# ControllerV2_0_2.net
KiCad netlist of a schematic drawn in Altium Designer
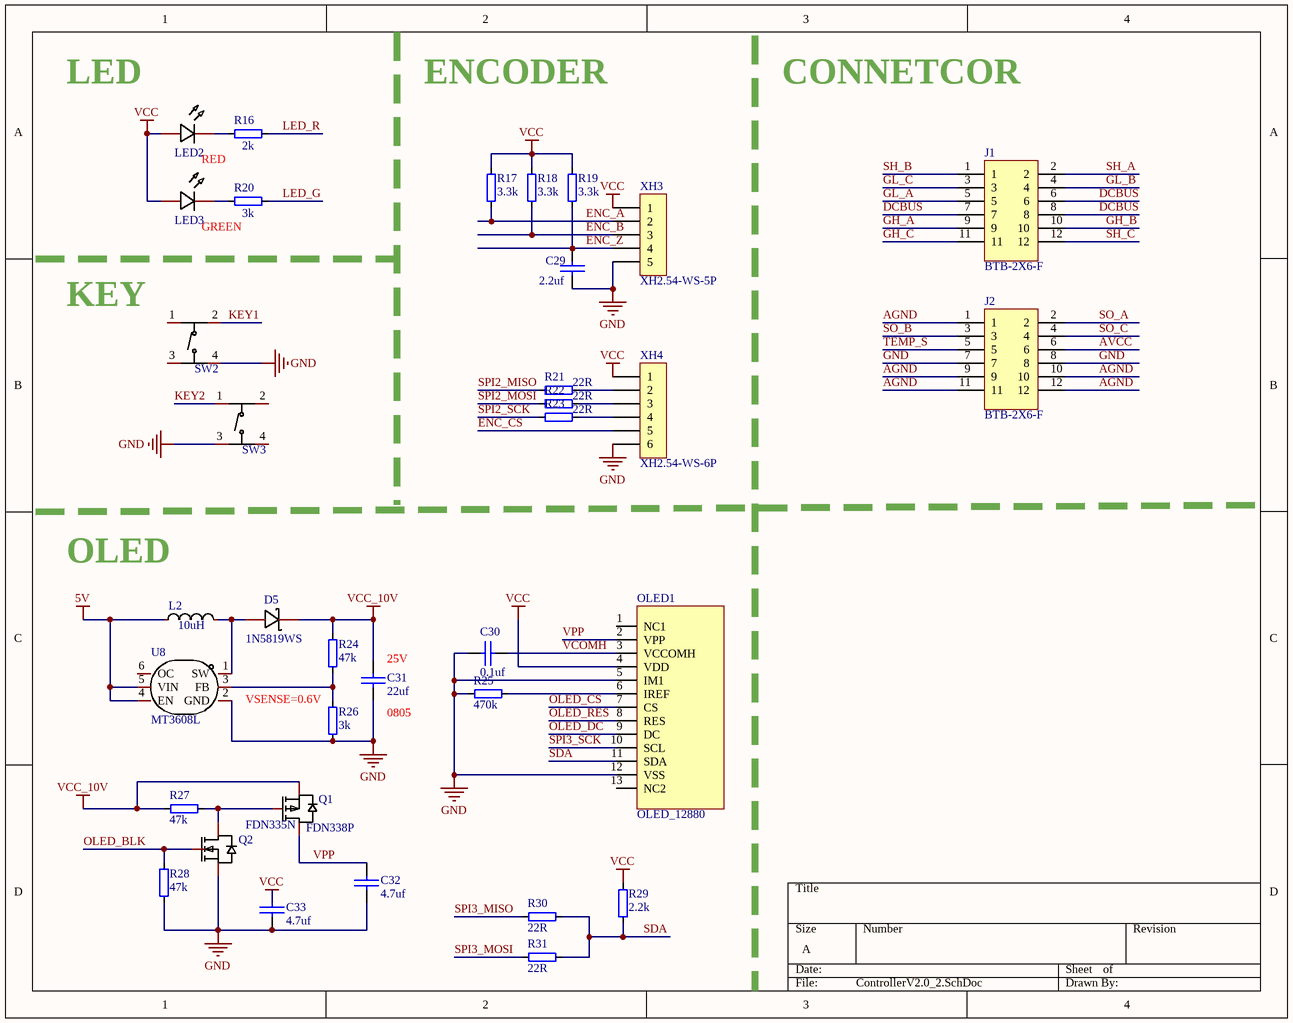
[diagram p0: ControllerV2.0_2.SchDoc]

(export (version "E")
  (design (tool "Eeschema 10.0.6"))
  (components
    (comp (ref "C29")
      (value "2.2uf")
      (footprint "0603C")
      (description "贴片电容")
      (libsource (lib "Controller") (part "CAP"))
    )
    (comp (ref "C30")
      (value "0.1uf")
      (footprint "0603C")
      (description "贴片电容")
      (libsource (lib "Controller") (part "CAP"))
    )
    (comp (ref "C31")
      (value "22uf")
      (footprint "0805C")
      (description "贴片电容")
      (libsource (lib "Controller") (part "CAP"))
    )
    (comp (ref "C32")
      (value "4.7uf")
      (footprint "0603C")
      (description "贴片电容")
      (libsource (lib "Controller") (part "CAP"))
    )
    (comp (ref "C33")
      (value "4.7uf")
      (footprint "0603C")
      (description "贴片电容")
      (libsource (lib "Controller") (part "CAP"))
    )
    (comp (ref "D5")
      (value "1N5819WS")
      (footprint "SOD-323")
      (description "肖特基二极管")
      (fields (field (name "MANUFACTURER") "Hottech(合科泰)"))
      (libsource (lib "Controller") (part "1N5819WS"))
    )
    (comp (ref "J1")
      (value "BTB-2X6-F")
      (footprint "BTB-F-0.8mm-2x6P")
      (description "0.8间距2x6P母座")
      (libsource (lib "Controller") (part "BTB-2X6-F"))
    )
    (comp (ref "J2")
      (value "BTB-2X6-F")
      (footprint "BTB-F-0.8mm-2x6P")
      (description "0.8间距2x6P母座")
      (libsource (lib "Controller") (part "BTB-2X6-F"))
    )
    (comp (ref "L2")
      (value "10uH")
      (footprint "IND-SMD_L3.0-W3.0_SWPA3010S")
      (description "电感值:10uH;精度:±20%;额定电流:920mA;")
      (fields (field (name "MANUFACTURER") "SXN(顺翔诺)") (field (name "MANUFACTURER PART") "SMDRI74-220M"))
      (libsource (lib "Controller") (part "SWPA3015S100MT"))
    )
    (comp (ref "LED2")
      (value "LED_0603-B")
      (footprint "LED_0603")
      (libsource (lib "Controller") (part "LED"))
    )
    (comp (ref "LED3")
      (value "LED_0603-B")
      (footprint "LED_0603")
      (libsource (lib "Controller") (part "LED"))
    )
    (comp (ref "OLED1")
      (value "OLED_12880")
      (footprint "OLED_12880")
      (description "OLED_128*80")
      (libsource (lib "Controller") (part "OLED_12880"))
    )
    (comp (ref "Q1")
      (value "FDN338P")
      (footprint "SOT-23-3")
      (description "P沟道 耐压:20V 电流:2A")
      (fields (field (name "MANUFACTURER") "TECH PUBLIC(台舟)"))
      (libsource (lib "Controller") (part "FDN338P"))
    )
    (comp (ref "Q2")
      (value "FDN335N")
      (footprint "SOT-23-3")
      (description "N沟道 耐压:20V 电流:1.7A")
      (fields (field (name "MANUFACTURER") "TECH PUBLIC(台舟)"))
      (libsource (lib "Controller") (part "FDN335N"))
    )
    (comp (ref "R16")
      (value "2k")
      (footprint "0603R")
      (description "贴片电阻")
      (libsource (lib "Controller") (part "RES"))
    )
    (comp (ref "R17")
      (value "3.3k")
      (footprint "0603R")
      (description "贴片电阻")
      (libsource (lib "Controller") (part "RES"))
    )
    (comp (ref "R18")
      (value "3.3k")
      (footprint "0603R")
      (description "贴片电阻")
      (libsource (lib "Controller") (part "RES"))
    )
    (comp (ref "R19")
      (value "3.3k")
      (footprint "0603R")
      (description "贴片电阻")
      (libsource (lib "Controller") (part "RES"))
    )
    (comp (ref "R20")
      (value "3k")
      (footprint "0603R")
      (description "贴片电阻")
      (libsource (lib "Controller") (part "RES"))
    )
    (comp (ref "R21")
      (value "22R")
      (footprint "0603R")
      (description "贴片电阻")
      (libsource (lib "Controller") (part "RES"))
    )
    (comp (ref "R22")
      (value "22R")
      (footprint "0603R")
      (description "贴片电阻")
      (libsource (lib "Controller") (part "RES"))
    )
    (comp (ref "R23")
      (value "22R")
      (footprint "0603R")
      (description "贴片电阻")
      (libsource (lib "Controller") (part "RES"))
    )
    (comp (ref "R24")
      (value "47k")
      (footprint "0603R")
      (description "贴片电阻")
      (libsource (lib "Controller") (part "RES"))
    )
    (comp (ref "R25")
      (value "470k")
      (footprint "0603R")
      (description "贴片电阻")
      (libsource (lib "Controller") (part "RES"))
    )
    (comp (ref "R26")
      (value "3k")
      (footprint "0603R")
      (description "贴片电阻")
      (libsource (lib "Controller") (part "RES"))
    )
    (comp (ref "R27")
      (value "47k")
      (footprint "0603R")
      (description "贴片电阻")
      (libsource (lib "Controller") (part "RES"))
    )
    (comp (ref "R28")
      (value "47k")
      (footprint "0603R")
      (description "贴片电阻")
      (libsource (lib "Controller") (part "RES"))
    )
    (comp (ref "R29")
      (value "2.2k")
      (footprint "0603R")
      (description "贴片电阻")
      (libsource (lib "Controller") (part "RES"))
    )
    (comp (ref "R30")
      (value "22R")
      (footprint "0603R")
      (description "贴片电阻")
      (libsource (lib "Controller") (part "RES"))
    )
    (comp (ref "R31")
      (value "22R")
      (footprint "0603R")
      (description "贴片电阻")
      (libsource (lib "Controller") (part "RES"))
    )
    (comp (ref "SW2")
      (value "TS-1187A-B-A-B")
      (footprint "TSW SMD-4*4*1.5")
      (description "轻触开关")
      (fields (field (name "MANUFACTURER") "XKB Connectivity(中国星坤)"))
      (libsource (lib "Controller") (part "TS-1187A-B-A-B"))
    )
    (comp (ref "SW3")
      (value "TS-1187A-B-A-B")
      (footprint "TSW SMD-4*4*1.5")
      (description "轻触开关")
      (fields (field (name "MANUFACTURER") "XKB Connectivity(中国星坤)"))
      (libsource (lib "Controller") (part "TS-1187A-B-A-B"))
    )
    (comp (ref "U8")
      (value "MT3608L")
      (footprint "SOT-23-6")
      (fields (field (name "MANUFACTURER") "西安航天民芯"))
      (libsource (lib "Controller") (part "MT3608L"))
    )
    (comp (ref "XH3")
      (value "XH2.54-WS-5P")
      (footprint "XH2.54-WS-5P")
      (libsource (lib "Controller") (part "XH2.54-WS-5P"))
    )
    (comp (ref "XH4")
      (value "XH2.54-WS-6P")
      (footprint "XH2.54-WS-6P")
      (libsource (lib "Controller") (part "XH2.54-WS-6P"))
    )
  )
  (nets
    (net (code "1") (name "/AGND") (class "Default")
      (node (ref "J2") (pin "1") (pinfunction "1_1") (pintype "passive"))
      (node (ref "J2") (pin "10") (pinfunction "10_10") (pintype "passive"))
      (node (ref "J2") (pin "11") (pinfunction "11_11") (pintype "passive"))
      (node (ref "J2") (pin "12") (pinfunction "12_12") (pintype "passive"))
      (node (ref "J2") (pin "9") (pinfunction "9_9") (pintype "passive"))
    )
    (net (code "2") (name "/AVCC") (class "Default")
      (node (ref "J2") (pin "6") (pinfunction "6_6") (pintype "passive"))
    )
    (net (code "3") (name "/DCBUS") (class "Default")
      (node (ref "J1") (pin "6") (pinfunction "6_6") (pintype "passive"))
      (node (ref "J1") (pin "7") (pinfunction "7_7") (pintype "passive"))
      (node (ref "J1") (pin "8") (pinfunction "8_8") (pintype "passive"))
    )
    (net (code "4") (name "/ENC_A") (class "Default")
      (node (ref "R17") (pin "1") (pinfunction "1_1") (pintype "passive"))
      (node (ref "XH3") (pin "2") (pinfunction "2_2") (pintype "passive"))
    )
    (net (code "5") (name "/ENC_B") (class "Default")
      (node (ref "R18") (pin "1") (pinfunction "1_1") (pintype "passive"))
      (node (ref "XH3") (pin "3") (pinfunction "3_3") (pintype "passive"))
    )
    (net (code "6") (name "/ENC_CS") (class "Default")
      (node (ref "XH4") (pin "5") (pinfunction "5_5") (pintype "passive"))
    )
    (net (code "7") (name "/ENC_Z") (class "Default")
      (node (ref "C29") (pin "1") (pinfunction "1_1") (pintype "passive"))
      (node (ref "R19") (pin "1") (pinfunction "1_1") (pintype "passive"))
      (node (ref "XH3") (pin "4") (pinfunction "4_4") (pintype "passive"))
    )
    (net (code "8") (name "/GH_A") (class "Default")
      (node (ref "J1") (pin "9") (pinfunction "9_9") (pintype "passive"))
    )
    (net (code "9") (name "/GH_B") (class "Default")
      (node (ref "J1") (pin "10") (pinfunction "10_10") (pintype "passive"))
    )
    (net (code "10") (name "/GH_C") (class "Default")
      (node (ref "J1") (pin "11") (pinfunction "11_11") (pintype "passive"))
    )
    (net (code "11") (name "/GL_A") (class "Default")
      (node (ref "J1") (pin "5") (pinfunction "5_5") (pintype "passive"))
    )
    (net (code "12") (name "/GL_B") (class "Default")
      (node (ref "J1") (pin "4") (pinfunction "4_4") (pintype "passive"))
    )
    (net (code "13") (name "/GL_C") (class "Default")
      (node (ref "J1") (pin "3") (pinfunction "3_3") (pintype "passive"))
    )
    (net (code "14") (name "/KEY1") (class "Default")
      (node (ref "SW2") (pin "2") (pinfunction "B_2") (pintype "passive"))
    )
    (net (code "15") (name "/KEY2") (class "Default")
      (node (ref "SW3") (pin "1") (pinfunction "A_1") (pintype "passive"))
    )
    (net (code "16") (name "/LED_G") (class "Default")
      (node (ref "R20") (pin "2") (pinfunction "2_2") (pintype "passive"))
    )
    (net (code "17") (name "/LED_R") (class "Default")
      (node (ref "R16") (pin "2") (pinfunction "2_2") (pintype "passive"))
    )
    (net (code "18") (name "/OLED_BLK") (class "Default")
      (node (ref "Q2") (pin "1") (pinfunction "G_1") (pintype "passive"))
      (node (ref "R28") (pin "2") (pinfunction "2_2") (pintype "passive"))
    )
    (net (code "19") (name "/OLED_CS") (class "Default")
      (node (ref "OLED1") (pin "7") (pinfunction "CS_7") (pintype "passive"))
    )
    (net (code "20") (name "/OLED_DC") (class "Default")
      (node (ref "OLED1") (pin "9") (pinfunction "DC_9") (pintype "passive"))
    )
    (net (code "21") (name "/OLED_RES") (class "Default")
      (node (ref "OLED1") (pin "8") (pinfunction "RES_8") (pintype "passive"))
    )
    (net (code "22") (name "/SDA") (class "Default")
      (node (ref "OLED1") (pin "11") (pinfunction "SDA_11") (pintype "passive"))
      (node (ref "R29") (pin "1") (pinfunction "1_1") (pintype "passive"))
      (node (ref "R30") (pin "2") (pinfunction "2_2") (pintype "passive"))
      (node (ref "R31") (pin "2") (pinfunction "2_2") (pintype "passive"))
    )
    (net (code "23") (name "/SH_A") (class "Default")
      (node (ref "J1") (pin "2") (pinfunction "2_2") (pintype "passive"))
    )
    (net (code "24") (name "/SH_B") (class "Default")
      (node (ref "J1") (pin "1") (pinfunction "1_1") (pintype "passive"))
    )
    (net (code "25") (name "/SH_C") (class "Default")
      (node (ref "J1") (pin "12") (pinfunction "12_12") (pintype "passive"))
    )
    (net (code "26") (name "/SO_A") (class "Default")
      (node (ref "J2") (pin "2") (pinfunction "2_2") (pintype "passive"))
    )
    (net (code "27") (name "/SO_B") (class "Default")
      (node (ref "J2") (pin "3") (pinfunction "3_3") (pintype "passive"))
    )
    (net (code "28") (name "/SO_C") (class "Default")
      (node (ref "J2") (pin "4") (pinfunction "4_4") (pintype "passive"))
    )
    (net (code "29") (name "/SPI2_MISO") (class "Default")
      (node (ref "R21") (pin "1") (pinfunction "1_1") (pintype "passive"))
    )
    (net (code "30") (name "/SPI2_MOSI") (class "Default")
      (node (ref "R22") (pin "1") (pinfunction "1_1") (pintype "passive"))
    )
    (net (code "31") (name "/SPI2_SCK") (class "Default")
      (node (ref "R23") (pin "1") (pinfunction "1_1") (pintype "passive"))
    )
    (net (code "32") (name "/SPI3_MISO") (class "Default")
      (node (ref "R30") (pin "1") (pinfunction "1_1") (pintype "passive"))
    )
    (net (code "33") (name "/SPI3_MOSI") (class "Default")
      (node (ref "R31") (pin "1") (pinfunction "1_1") (pintype "passive"))
    )
    (net (code "34") (name "/SPI3_SCK") (class "Default")
      (node (ref "OLED1") (pin "10") (pinfunction "SCL_10") (pintype "passive"))
    )
    (net (code "35") (name "/TEMP_S") (class "Default")
      (node (ref "J2") (pin "5") (pinfunction "5_5") (pintype "passive"))
    )
    (net (code "36") (name "/VCOMH") (class "Default")
      (node (ref "C30") (pin "2") (pinfunction "2_2") (pintype "passive"))
      (node (ref "OLED1") (pin "3") (pinfunction "VCCOMH_3") (pintype "passive"))
    )
    (net (code "37") (name "/VPP") (class "Default")
      (node (ref "C32") (pin "1") (pinfunction "1_1") (pintype "passive"))
      (node (ref "OLED1") (pin "2") (pinfunction "VPP_2") (pintype "passive"))
      (node (ref "Q1") (pin "3") (pinfunction "D_3") (pintype "passive"))
    )
    (net (code "38") (name "5V") (class "Default")
      (node (ref "L2") (pin "1") (pinfunction "1_1") (pintype "passive"))
      (node (ref "U8") (pin "4") (pinfunction "EN_4") (pintype "passive"))
      (node (ref "U8") (pin "5") (pinfunction "VIN_5") (pintype "passive"))
    )
    (net (code "39") (name "GND") (class "Default")
      (node (ref "C29") (pin "2") (pinfunction "2_2") (pintype "passive"))
      (node (ref "C30") (pin "1") (pinfunction "1_1") (pintype "passive"))
      (node (ref "C31") (pin "2") (pinfunction "2_2") (pintype "passive"))
      (node (ref "C32") (pin "2") (pinfunction "2_2") (pintype "passive"))
      (node (ref "C33") (pin "2") (pinfunction "2_2") (pintype "passive"))
      (node (ref "J2") (pin "7") (pinfunction "7_7") (pintype "passive"))
      (node (ref "J2") (pin "8") (pinfunction "8_8") (pintype "passive"))
      (node (ref "OLED1") (pin "12") (pinfunction "VSS_12") (pintype "passive"))
      (node (ref "OLED1") (pin "5") (pinfunction "IM1_5") (pintype "passive"))
      (node (ref "Q2") (pin "2") (pinfunction "S_2") (pintype "passive"))
      (node (ref "R25") (pin "1") (pinfunction "1_1") (pintype "passive"))
      (node (ref "R26") (pin "1") (pinfunction "1_1") (pintype "passive"))
      (node (ref "R28") (pin "1") (pinfunction "1_1") (pintype "passive"))
      (node (ref "SW2") (pin "4") (pinfunction "D_4") (pintype "passive"))
      (node (ref "SW3") (pin "3") (pinfunction "C_3") (pintype "passive"))
      (node (ref "U8") (pin "2") (pinfunction "GND_2") (pintype "passive"))
      (node (ref "XH3") (pin "5") (pinfunction "5_5") (pintype "passive"))
      (node (ref "XH4") (pin "6") (pinfunction "6_6") (pintype "passive"))
    )
    (net (code "40") (name "Net-(D5-A)") (class "Default")
      (node (ref "D5") (pin "2") (pinfunction "A_2") (pintype "passive"))
      (node (ref "L2") (pin "2") (pinfunction "2_2") (pintype "passive"))
      (node (ref "U8") (pin "1") (pinfunction "SW_1") (pintype "passive"))
    )
    (net (code "41") (name "Net-(LED2-C)") (class "Default")
      (node (ref "LED2") (pin "1") (pinfunction "C_1") (pintype "passive"))
      (node (ref "R16") (pin "1") (pinfunction "1_1") (pintype "passive"))
    )
    (net (code "42") (name "Net-(LED3-C)") (class "Default")
      (node (ref "LED3") (pin "1") (pinfunction "C_1") (pintype "passive"))
      (node (ref "R20") (pin "1") (pinfunction "1_1") (pintype "passive"))
    )
    (net (code "43") (name "Net-(OLED1-IREF)") (class "Default")
      (node (ref "OLED1") (pin "6") (pinfunction "IREF_6") (pintype "passive"))
      (node (ref "R25") (pin "2") (pinfunction "2_2") (pintype "passive"))
    )
    (net (code "44") (name "Net-(Q1-G)") (class "Default")
      (node (ref "Q1") (pin "1") (pinfunction "G_1") (pintype "passive"))
      (node (ref "Q2") (pin "3") (pinfunction "D_3") (pintype "passive"))
      (node (ref "R27") (pin "2") (pinfunction "2_2") (pintype "passive"))
    )
    (net (code "45") (name "Net-(R21-Pad2)") (class "Default")
      (node (ref "R21") (pin "2") (pinfunction "2_2") (pintype "passive"))
      (node (ref "XH4") (pin "2") (pinfunction "2_2") (pintype "passive"))
    )
    (net (code "46") (name "Net-(R22-Pad2)") (class "Default")
      (node (ref "R22") (pin "2") (pinfunction "2_2") (pintype "passive"))
      (node (ref "XH4") (pin "3") (pinfunction "3_3") (pintype "passive"))
    )
    (net (code "47") (name "Net-(R23-Pad2)") (class "Default")
      (node (ref "R23") (pin "2") (pinfunction "2_2") (pintype "passive"))
      (node (ref "XH4") (pin "4") (pinfunction "4_4") (pintype "passive"))
    )
    (net (code "48") (name "Net-(U8-FB)") (class "Default")
      (node (ref "R24") (pin "1") (pinfunction "1_1") (pintype "passive"))
      (node (ref "R26") (pin "2") (pinfunction "2_2") (pintype "passive"))
      (node (ref "U8") (pin "3") (pinfunction "FB_3") (pintype "passive"))
    )
    (net (code "49") (name "VCC") (class "Default")
      (node (ref "C33") (pin "1") (pinfunction "1_1") (pintype "passive"))
      (node (ref "LED2") (pin "2") (pinfunction "A_2") (pintype "passive"))
      (node (ref "LED3") (pin "2") (pinfunction "A_2") (pintype "passive"))
      (node (ref "OLED1") (pin "4") (pinfunction "VDD_4") (pintype "passive"))
      (node (ref "R17") (pin "2") (pinfunction "2_2") (pintype "passive"))
      (node (ref "R18") (pin "2") (pinfunction "2_2") (pintype "passive"))
      (node (ref "R19") (pin "2") (pinfunction "2_2") (pintype "passive"))
      (node (ref "R29") (pin "2") (pinfunction "2_2") (pintype "passive"))
      (node (ref "XH3") (pin "1") (pinfunction "1_1") (pintype "passive"))
      (node (ref "XH4") (pin "1") (pinfunction "1_1") (pintype "passive"))
    )
    (net (code "50") (name "VCC_10V") (class "Default")
      (node (ref "C31") (pin "1") (pinfunction "1_1") (pintype "passive"))
      (node (ref "D5") (pin "1") (pinfunction "K_1") (pintype "passive"))
      (node (ref "Q1") (pin "2") (pinfunction "S_2") (pintype "passive"))
      (node (ref "R24") (pin "2") (pinfunction "2_2") (pintype "passive"))
      (node (ref "R27") (pin "1") (pinfunction "1_1") (pintype "passive"))
    )
    (net (code "51") (name "unconnected-(OLED1-NC1-Pad1)") (class "Default")
      (node (ref "OLED1") (pin "1") (pinfunction "NC1_1") (pintype "passive"))
    )
    (net (code "52") (name "unconnected-(OLED1-NC2-Pad13)") (class "Default")
      (node (ref "OLED1") (pin "13") (pinfunction "NC2_13") (pintype "passive"))
    )
    (net (code "53") (name "unconnected-(SW2-A-Pad1)") (class "Default")
      (node (ref "SW2") (pin "1") (pinfunction "A_1") (pintype "passive"))
    )
    (net (code "54") (name "unconnected-(SW2-C-Pad3)") (class "Default")
      (node (ref "SW2") (pin "3") (pinfunction "C_3") (pintype "passive"))
    )
    (net (code "55") (name "unconnected-(SW3-B-Pad2)") (class "Default")
      (node (ref "SW3") (pin "2") (pinfunction "B_2") (pintype "passive"))
    )
    (net (code "56") (name "unconnected-(SW3-D-Pad4)") (class "Default")
      (node (ref "SW3") (pin "4") (pinfunction "D_4") (pintype "passive"))
    )
    (net (code "57") (name "unconnected-(U8-OC-Pad6)") (class "Default")
      (node (ref "U8") (pin "6") (pinfunction "OC_6") (pintype "passive"))
    )
  )
)
